# main.net
KiCad netlist of a schematic drawn in Altium Designer
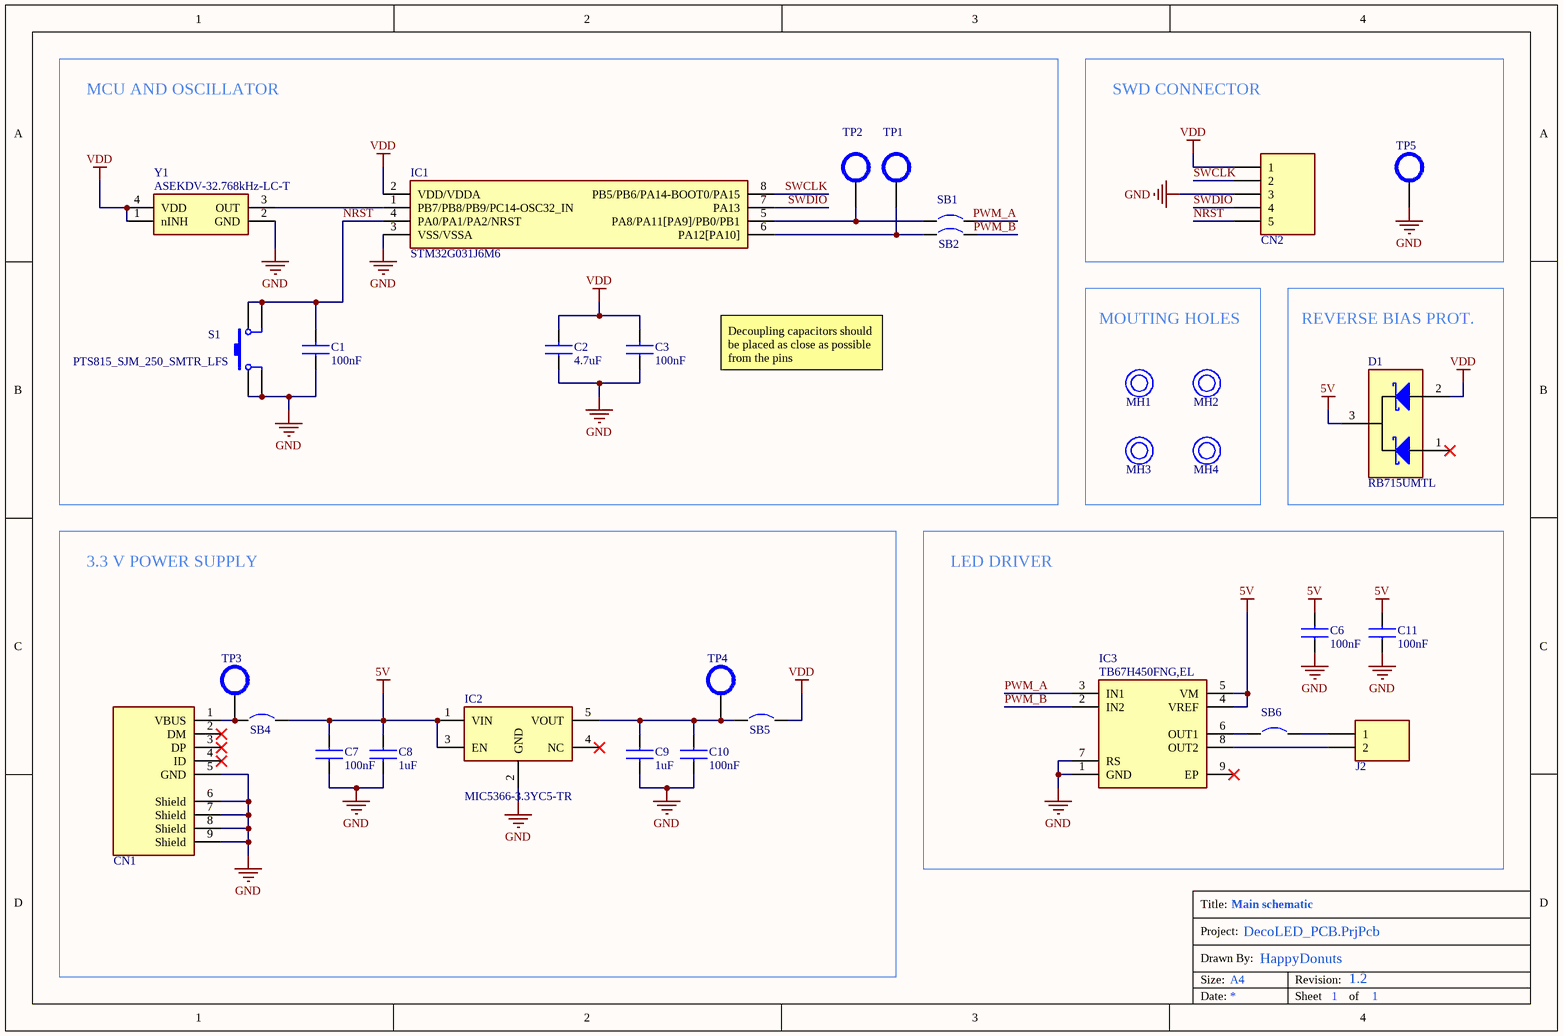
[diagram p0: main.SchDoc]

(export (version "E")
  (design (tool "Eeschema 10.0.6"))
  (components
    (comp (ref "C1")
      (value "100nF")
      (footprint "DecoLED:CAPC2012X94N")
      (description "Capacitor")
      (fields
        (field (name "MANUFACTURER_PART_NUMBER") "C0805C104K5RAC7411")
        (field (name "MOUSER PART NUMBER") "80-C0805C104K5RACLR")
      )
      (libsource (lib "DecoLED") (part "C0805C104K5RAC7411"))
    )
    (comp (ref "C2")
      (value "4.7uF")
      (footprint "DecoLED:CAPC2012X135N")
      (description "Capacitor")
      (fields
        (field (name "MANUFACTURER_PART_NUMBER") "CL21A475KPFNNNE")
        (field (name "MOUSER PART NUMBER") "187-CL21A475KPFNNNE")
      )
      (libsource (lib "DecoLED") (part "CL21A475KPFNNNE"))
    )
    (comp (ref "C3")
      (value "100nF")
      (footprint "DecoLED:CAPC2012X94N")
      (description "Capacitor")
      (fields
        (field (name "MANUFACTURER_PART_NUMBER") "C0805C104K5RAC7411")
        (field (name "MOUSER PART NUMBER") "80-C0805C104K5RACLR")
      )
      (libsource (lib "DecoLED") (part "C0805C104K5RAC7411"))
    )
    (comp (ref "C6")
      (value "100nF")
      (footprint "PcbLib1:CAPC2012X94N")
      (description "Capacitor")
      (fields
        (field (name "MANUFACTURER_PART_NUMBER") "C0805C104K5RAC7411")
        (field (name "MOUSER PART NUMBER") "80-C0805C104K5RACLR")
      )
      (libsource (lib "Schlib1") (part "C0805C104K5RAC7411"))
    )
    (comp (ref "C7")
      (value "100nF")
      (footprint "PcbLib1:CAPC2012X94N")
      (description "Capacitor")
      (fields
        (field (name "MANUFACTURER_PART_NUMBER") "C0805C104K5RAC7411")
        (field (name "MOUSER PART NUMBER") "80-C0805C104K5RACLR")
      )
      (libsource (lib "Schlib1") (part "C0805C104K5RAC7411"))
    )
    (comp (ref "C8")
      (value "1uF")
      (footprint "PcbLib1:CAPC2012X135N")
      (description "Capacitor")
      (fields
        (field (name "MANUFACTURER_PART_NUMBER") "885012107015")
        (field (name "MOUSER PART NUMBER") "710-885012107015")
      )
      (libsource (lib "Schlib1") (part "885012107015"))
    )
    (comp (ref "C9")
      (value "1uF")
      (footprint "PcbLib1:CAPC2012X135N")
      (description "Capacitor")
      (fields
        (field (name "MANUFACTURER_PART_NUMBER") "885012107015")
        (field (name "MOUSER PART NUMBER") "710-885012107015")
      )
      (libsource (lib "Schlib1") (part "885012107015"))
    )
    (comp (ref "C10")
      (value "100nF")
      (footprint "PcbLib1:CAPC2012X94N")
      (description "Capacitor")
      (fields
        (field (name "MANUFACTURER_PART_NUMBER") "C0805C104K5RAC7411")
        (field (name "MOUSER PART NUMBER") "80-C0805C104K5RACLR")
      )
      (libsource (lib "Schlib1") (part "C0805C104K5RAC7411"))
    )
    (comp (ref "C11")
      (value "100nF")
      (footprint "PcbLib1:CAPC2012X94N")
      (description "Capacitor")
      (fields
        (field (name "MANUFACTURER_PART_NUMBER") "C0805C104K5RAC7411")
        (field (name "MOUSER PART NUMBER") "80-C0805C104K5RACLR")
      )
      (libsource (lib "Schlib1") (part "C0805C104K5RAC7411"))
    )
    (comp (ref "CN1")
      (value "920-E52A2021S10100")
      (footprint "DecoLED:USB307530A")
      (description "USB connector")
      (fields (field (name "ARROW PART NUMBER") "TB67H450FNG,EL"))
      (libsource (lib "DecoLED") (part "920-E52A2021S10100"))
    )
    (comp (ref "CN2")
      (value "CN_5PIN")
      (footprint "DecoLED:CN_5PIN")
      (description "Connector")
      (libsource (lib "DecoLED") (part "CN_5PIN"))
    )
    (comp (ref "D1")
      (value "RB715UMTL")
      (footprint "DecoLED:DAN217UMTL")
      (description "Schottky Diode")
      (fields (field (name "MOUSER PART NUMBER") "755-RB715UMTL"))
      (libsource (lib "DecoLED") (part "RB715UMTL"))
    )
    (comp (ref "IC1")
      (value "STM32G031J6M6")
      (footprint "DecoLED:SOIC127P600X175-8N")
      (description "Integrated Circuit")
      (fields (field (name "MOUSER PART NUMBER") "511-STM32G031J6M6"))
      (libsource (lib "DecoLED") (part "STM32G031J6M6"))
    )
    (comp (ref "IC2")
      (value "MIC5366-3.3YC5-TR")
      (footprint "DecoLED:SOT65P210X110-5N")
      (description "LDO")
      (fields
        (field (name "MOUSER PART NUMBER") "998-MIC5366-3.3YC5TR")
        (field (name "ARROW PART NUMBER") "MIC5365-3.3YC5-TR")
      )
      (libsource (lib "DecoLED") (part "MIC5366-3.3YC5-TR"))
    )
    (comp (ref "IC3")
      (value "TB67H450FNG,EL")
      (footprint "PcbLib1:SOIC127P600X175-9N")
      (description "Integrated Circuit")
      (fields (field (name "MOUSER PART NUMBER") "757-TB67H450FNGEL"))
      (libsource (lib "Schlib1") (part "TB67H450FNG,EL"))
    )
    (comp (ref "J2")
      (value "B2B-PH-K-S_LF__SN_")
      (footprint "PcbLib1:SHDR2W50P0X200_1X2_590X450X600P")
      (description "Connector")
      (fields (field (name "MANUFACTURER_PART_NUMBER") "B2B-PH-K-S(LF)(SN)"))
      (libsource (lib "Schlib1") (part "B2B-PH-K-S_LF__SN_"))
    )
    (comp (ref "MH1")
      (value "MOUNTING_HOLE_NP")
      (footprint "MOUNTING_HOLE_NP")
      (description "Mounting hole")
      (libsource (lib "Schlib1") (part "MOUNTING_HOLE_NP"))
    )
    (comp (ref "MH2")
      (value "MOUNTING_HOLE_NP")
      (footprint "MOUNTING_HOLE_NP")
      (description "Mounting hole")
      (libsource (lib "Schlib1") (part "MOUNTING_HOLE_NP"))
    )
    (comp (ref "MH3")
      (value "MOUNTING_HOLE_NP")
      (footprint "MOUNTING_HOLE_NP")
      (description "Mounting hole")
      (libsource (lib "Schlib1") (part "MOUNTING_HOLE_NP"))
    )
    (comp (ref "MH4")
      (value "MOUNTING_HOLE_NP")
      (footprint "MOUNTING_HOLE_NP")
      (description "Mounting hole")
      (libsource (lib "Schlib1") (part "MOUNTING_HOLE_NP"))
    )
    (comp (ref "S1")
      (value "PTS815_SJM_250_SMTR_LFS")
      (footprint "DecoLED:EVP-BT3G4A000")
      (description "Switch")
      (fields
        (field (name "MANUFACTURER_PART_NUMBER") "PTS815 SJM 250 SMTR LFS")
        (field (name "MOUSER PART NUMBER") "611-PTS815SJM250SMTR")
      )
      (libsource (lib "DecoLED") (part "PTS815_SJM_250_SMTR_LFS"))
    )
    (comp (ref "SB1")
      (value "RC0805FR-070RL")
      (footprint "PcbLib1:RESC2012X60N")
      (description "Jumper (0 ohm)")
      (fields (field (name "MOUSER PART NUMBER") "603-RC0805FR-070RL"))
      (libsource (lib "Schlib1") (part "RC0805FR-070RL"))
    )
    (comp (ref "SB2")
      (value "RC0805FR-070RL")
      (footprint "PcbLib1:RESC2012X60N")
      (description "Jumper (0 ohm)")
      (fields (field (name "MOUSER PART NUMBER") "603-RC0805FR-070RL"))
      (libsource (lib "Schlib1") (part "RC0805FR-070RL"))
    )
    (comp (ref "SB4")
      (value "RC0805FR-070RL")
      (footprint "PcbLib1:RESC2012X60N")
      (description "Jumper (0 ohm)")
      (fields (field (name "MOUSER PART NUMBER") "603-RC0805FR-070RL"))
      (libsource (lib "") (part "RC0805FR-070RL_1"))
    )
    (comp (ref "SB5")
      (value "RC0805FR-070RL")
      (footprint "PcbLib1:RESC2012X60N")
      (description "Jumper (0 ohm)")
      (fields (field (name "MOUSER PART NUMBER") "603-RC0805FR-070RL"))
      (libsource (lib "") (part "RC0805FR-070RL_1"))
    )
    (comp (ref "SB6")
      (value "RC0805FR-070RL")
      (footprint "PcbLib1:RESC2012X60N")
      (description "Jumper (0 ohm)")
      (fields (field (name "MOUSER PART NUMBER") "603-RC0805FR-070RL"))
      (libsource (lib "") (part "RC0805FR-070RL_1"))
    )
    (comp (ref "TP1")
      (value "TEST_POINT")
      (footprint "TEST_POINT")
      (description "Test point")
      (libsource (lib "Schlib1") (part "TEST_POINT"))
    )
    (comp (ref "TP2")
      (value "TEST_POINT")
      (footprint "TEST_POINT")
      (description "Test point")
      (libsource (lib "Schlib1") (part "TEST_POINT"))
    )
    (comp (ref "TP3")
      (value "TEST_POINT")
      (footprint "TEST_POINT")
      (description "Test point")
      (libsource (lib "Schlib1") (part "TEST_POINT"))
    )
    (comp (ref "TP4")
      (value "TEST_POINT")
      (footprint "TEST_POINT")
      (description "Test point")
      (libsource (lib "Schlib1") (part "TEST_POINT"))
    )
    (comp (ref "TP5")
      (value "TEST_POINT")
      (footprint "TEST_POINT")
      (description "Test point")
      (libsource (lib "Schlib1") (part "TEST_POINT"))
    )
    (comp (ref "Y1")
      (value "ASEKDV-32.768kHz-LC-T")
      (footprint "DecoLED:ASEKDV-32.768kHz-LC-T")
      (description "Crystal or Oscillator")
      (fields (field (name "MOUSER PART NUMBER") "815-ASEKDV32768KHLCT"))
      (libsource (lib "DecoLED") (part "ASEKDV-32.768kHz-LC-T"))
    )
  )
  (nets
    (net (code "1") (name "/NRST") (class "Default")
      (node (ref "C1") (pin "2") (pinfunction "2_2") (pintype "passive"))
      (node (ref "CN2") (pin "5") (pinfunction "5_5") (pintype "passive"))
      (node (ref "IC1") (pin "4") (pinfunction "PA0/PA1/PA2/NRST_4") (pintype "passive"))
      (node (ref "S1") (pin "3") (pinfunction "3_3") (pintype "passive"))
      (node (ref "S1") (pin "4") (pinfunction "4_4") (pintype "passive"))
    )
    (net (code "2") (name "/PWM_A") (class "Default")
      (node (ref "IC3") (pin "3") (pinfunction "IN1_3") (pintype "passive"))
      (node (ref "SB1") (pin "1") (pinfunction "1_1") (pintype "passive"))
    )
    (net (code "3") (name "/PWM_B") (class "Default")
      (node (ref "IC3") (pin "2") (pinfunction "IN2_2") (pintype "passive"))
      (node (ref "SB2") (pin "1") (pinfunction "1_1") (pintype "passive"))
    )
    (net (code "4") (name "/SWCLK") (class "Default")
      (node (ref "CN2") (pin "2") (pinfunction "2_2") (pintype "passive"))
      (node (ref "IC1") (pin "8") (pinfunction "PB5/PB6/PA14-BOOT0/PA15_8") (pintype "passive"))
    )
    (net (code "5") (name "/SWDIO") (class "Default")
      (node (ref "CN2") (pin "4") (pinfunction "4_4") (pintype "passive"))
      (node (ref "IC1") (pin "7") (pinfunction "PA13_7") (pintype "passive"))
    )
    (net (code "6") (name "5V") (class "Default")
      (node (ref "C11") (pin "2") (pinfunction "2_2") (pintype "passive"))
      (node (ref "C6") (pin "2") (pinfunction "2_2") (pintype "passive"))
      (node (ref "C7") (pin "2") (pinfunction "2_2") (pintype "passive"))
      (node (ref "C8") (pin "2") (pinfunction "2_2") (pintype "passive"))
      (node (ref "D1") (pin "3") (pinfunction "COM_A_3") (pintype "passive"))
      (node (ref "IC2") (pin "1") (pinfunction "VIN_1") (pintype "power_in"))
      (node (ref "IC2") (pin "3") (pinfunction "EN_3") (pintype "passive"))
      (node (ref "IC3") (pin "4") (pinfunction "VREF_4") (pintype "passive"))
      (node (ref "IC3") (pin "5") (pinfunction "VM_5") (pintype "passive"))
      (node (ref "SB4") (pin "2") (pinfunction "2_2") (pintype "passive"))
    )
    (net (code "7") (name "GND") (class "Default")
      (node (ref "C1") (pin "1") (pinfunction "1_1") (pintype "passive"))
      (node (ref "C10") (pin "1") (pinfunction "1_1") (pintype "passive"))
      (node (ref "C11") (pin "1") (pinfunction "1_1") (pintype "passive"))
      (node (ref "C2") (pin "1") (pinfunction "1_1") (pintype "passive"))
      (node (ref "C3") (pin "1") (pinfunction "1_1") (pintype "passive"))
      (node (ref "C6") (pin "1") (pinfunction "1_1") (pintype "passive"))
      (node (ref "C7") (pin "1") (pinfunction "1_1") (pintype "passive"))
      (node (ref "C8") (pin "1") (pinfunction "1_1") (pintype "passive"))
      (node (ref "C9") (pin "1") (pinfunction "1_1") (pintype "passive"))
      (node (ref "CN1") (pin "5") (pinfunction "GND_5") (pintype "passive"))
      (node (ref "CN1") (pin "6") (pinfunction "Shield_6") (pintype "passive"))
      (node (ref "CN1") (pin "7") (pinfunction "Shield_7") (pintype "passive"))
      (node (ref "CN1") (pin "8") (pinfunction "Shield_8") (pintype "passive"))
      (node (ref "CN1") (pin "9") (pinfunction "Shield_9") (pintype "passive"))
      (node (ref "CN2") (pin "3") (pinfunction "3_3") (pintype "passive"))
      (node (ref "IC1") (pin "3") (pinfunction "VSS/VSSA_3") (pintype "passive"))
      (node (ref "IC2") (pin "2") (pinfunction "GND_2") (pintype "power_in"))
      (node (ref "IC3") (pin "1") (pinfunction "GND_1") (pintype "passive"))
      (node (ref "IC3") (pin "7") (pinfunction "RS_7") (pintype "passive"))
      (node (ref "S1") (pin "1") (pinfunction "1_1") (pintype "passive"))
      (node (ref "S1") (pin "2") (pinfunction "2_2") (pintype "passive"))
      (node (ref "TP5") (pin "TP") (pinfunction "TP_TP") (pintype "passive"))
      (node (ref "Y1") (pin "2") (pinfunction "GND_2") (pintype "passive"))
    )
    (net (code "8") (name "Net-(CN1-VBUS)") (class "Default")
      (node (ref "CN1") (pin "1") (pinfunction "VBUS_1") (pintype "passive"))
      (node (ref "SB4") (pin "1") (pinfunction "1_1") (pintype "passive"))
      (node (ref "TP3") (pin "TP") (pinfunction "TP_TP") (pintype "passive"))
    )
    (net (code "9") (name "Net-(IC1-PA8{slash}PA11[PA9]{slash}PB0{slash}PB1)") (class "Default")
      (node (ref "IC1") (pin "5") (pinfunction "PA8/PA11[PA9]/PB0/PB1_5") (pintype "passive"))
      (node (ref "SB1") (pin "2") (pinfunction "2_2") (pintype "passive"))
      (node (ref "TP2") (pin "TP") (pinfunction "TP_TP") (pintype "passive"))
    )
    (net (code "10") (name "Net-(IC1-PA12[PA10])") (class "Default")
      (node (ref "IC1") (pin "6") (pinfunction "PA12[PA10]_6") (pintype "passive"))
      (node (ref "SB2") (pin "2") (pinfunction "2_2") (pintype "passive"))
      (node (ref "TP1") (pin "TP") (pinfunction "TP_TP") (pintype "passive"))
    )
    (net (code "11") (name "Net-(IC1-PB7{slash}PB8{slash}PB9{slash}PC14-OSC32_IN)") (class "Default")
      (node (ref "IC1") (pin "1") (pinfunction "PB7/PB8/PB9/PC14-OSC32_IN_1") (pintype "passive"))
      (node (ref "Y1") (pin "3") (pinfunction "OUT_3") (pintype "passive"))
    )
    (net (code "12") (name "Net-(IC2-VOUT)") (class "Default")
      (node (ref "C10") (pin "2") (pinfunction "2_2") (pintype "passive"))
      (node (ref "C9") (pin "2") (pinfunction "2_2") (pintype "passive"))
      (node (ref "IC2") (pin "5") (pinfunction "VOUT_5") (pintype "passive"))
      (node (ref "SB5") (pin "1") (pinfunction "1_1") (pintype "passive"))
      (node (ref "TP4") (pin "TP") (pinfunction "TP_TP") (pintype "passive"))
    )
    (net (code "13") (name "Net-(IC3-OUT1)") (class "Default")
      (node (ref "IC3") (pin "6") (pinfunction "OUT1_6") (pintype "passive"))
      (node (ref "SB6") (pin "1") (pinfunction "1_1") (pintype "passive"))
    )
    (net (code "14") (name "Net-(IC3-OUT2)") (class "Default")
      (node (ref "IC3") (pin "8") (pinfunction "OUT2_8") (pintype "passive"))
      (node (ref "J2") (pin "2") (pinfunction "2_2") (pintype "passive"))
    )
    (net (code "15") (name "Net-(J2-Pad1)") (class "Default")
      (node (ref "J2") (pin "1") (pinfunction "1_1") (pintype "passive"))
      (node (ref "SB6") (pin "2") (pinfunction "2_2") (pintype "passive"))
    )
    (net (code "16") (name "VDD") (class "Default")
      (node (ref "C2") (pin "2") (pinfunction "2_2") (pintype "passive"))
      (node (ref "C3") (pin "2") (pinfunction "2_2") (pintype "passive"))
      (node (ref "CN2") (pin "1") (pinfunction "1_1") (pintype "passive"))
      (node (ref "D1") (pin "2") (pinfunction "K_2_2") (pintype "passive"))
      (node (ref "IC1") (pin "2") (pinfunction "VDD/VDDA_2") (pintype "passive"))
      (node (ref "SB5") (pin "2") (pinfunction "2_2") (pintype "passive"))
      (node (ref "Y1") (pin "1") (pinfunction "nINH_1") (pintype "passive"))
      (node (ref "Y1") (pin "4") (pinfunction "VDD_4") (pintype "passive"))
    )
    (net (code "17") (name "unconnected-(CN1-DM-Pad2)") (class "Default")
      (node (ref "CN1") (pin "2") (pinfunction "DM_2") (pintype "passive+no_connect"))
    )
    (net (code "18") (name "unconnected-(CN1-DP-Pad3)") (class "Default")
      (node (ref "CN1") (pin "3") (pinfunction "DP_3") (pintype "passive+no_connect"))
    )
    (net (code "19") (name "unconnected-(CN1-ID-Pad4)") (class "Default")
      (node (ref "CN1") (pin "4") (pinfunction "ID_4") (pintype "passive+no_connect"))
    )
    (net (code "20") (name "unconnected-(D1-K_1-Pad1)") (class "Default")
      (node (ref "D1") (pin "1") (pinfunction "K_1_1") (pintype "passive+no_connect"))
    )
    (net (code "21") (name "unconnected-(IC2-NC-Pad4)") (class "Default")
      (node (ref "IC2") (pin "4") (pinfunction "NC_4") (pintype "passive+no_connect"))
    )
    (net (code "22") (name "unconnected-(IC3-EP-Pad9)") (class "Default")
      (node (ref "IC3") (pin "9") (pinfunction "EP_9") (pintype "passive+no_connect"))
    )
  )
)
